# top.net
KiCad netlist of a schematic drawn in EAGLE
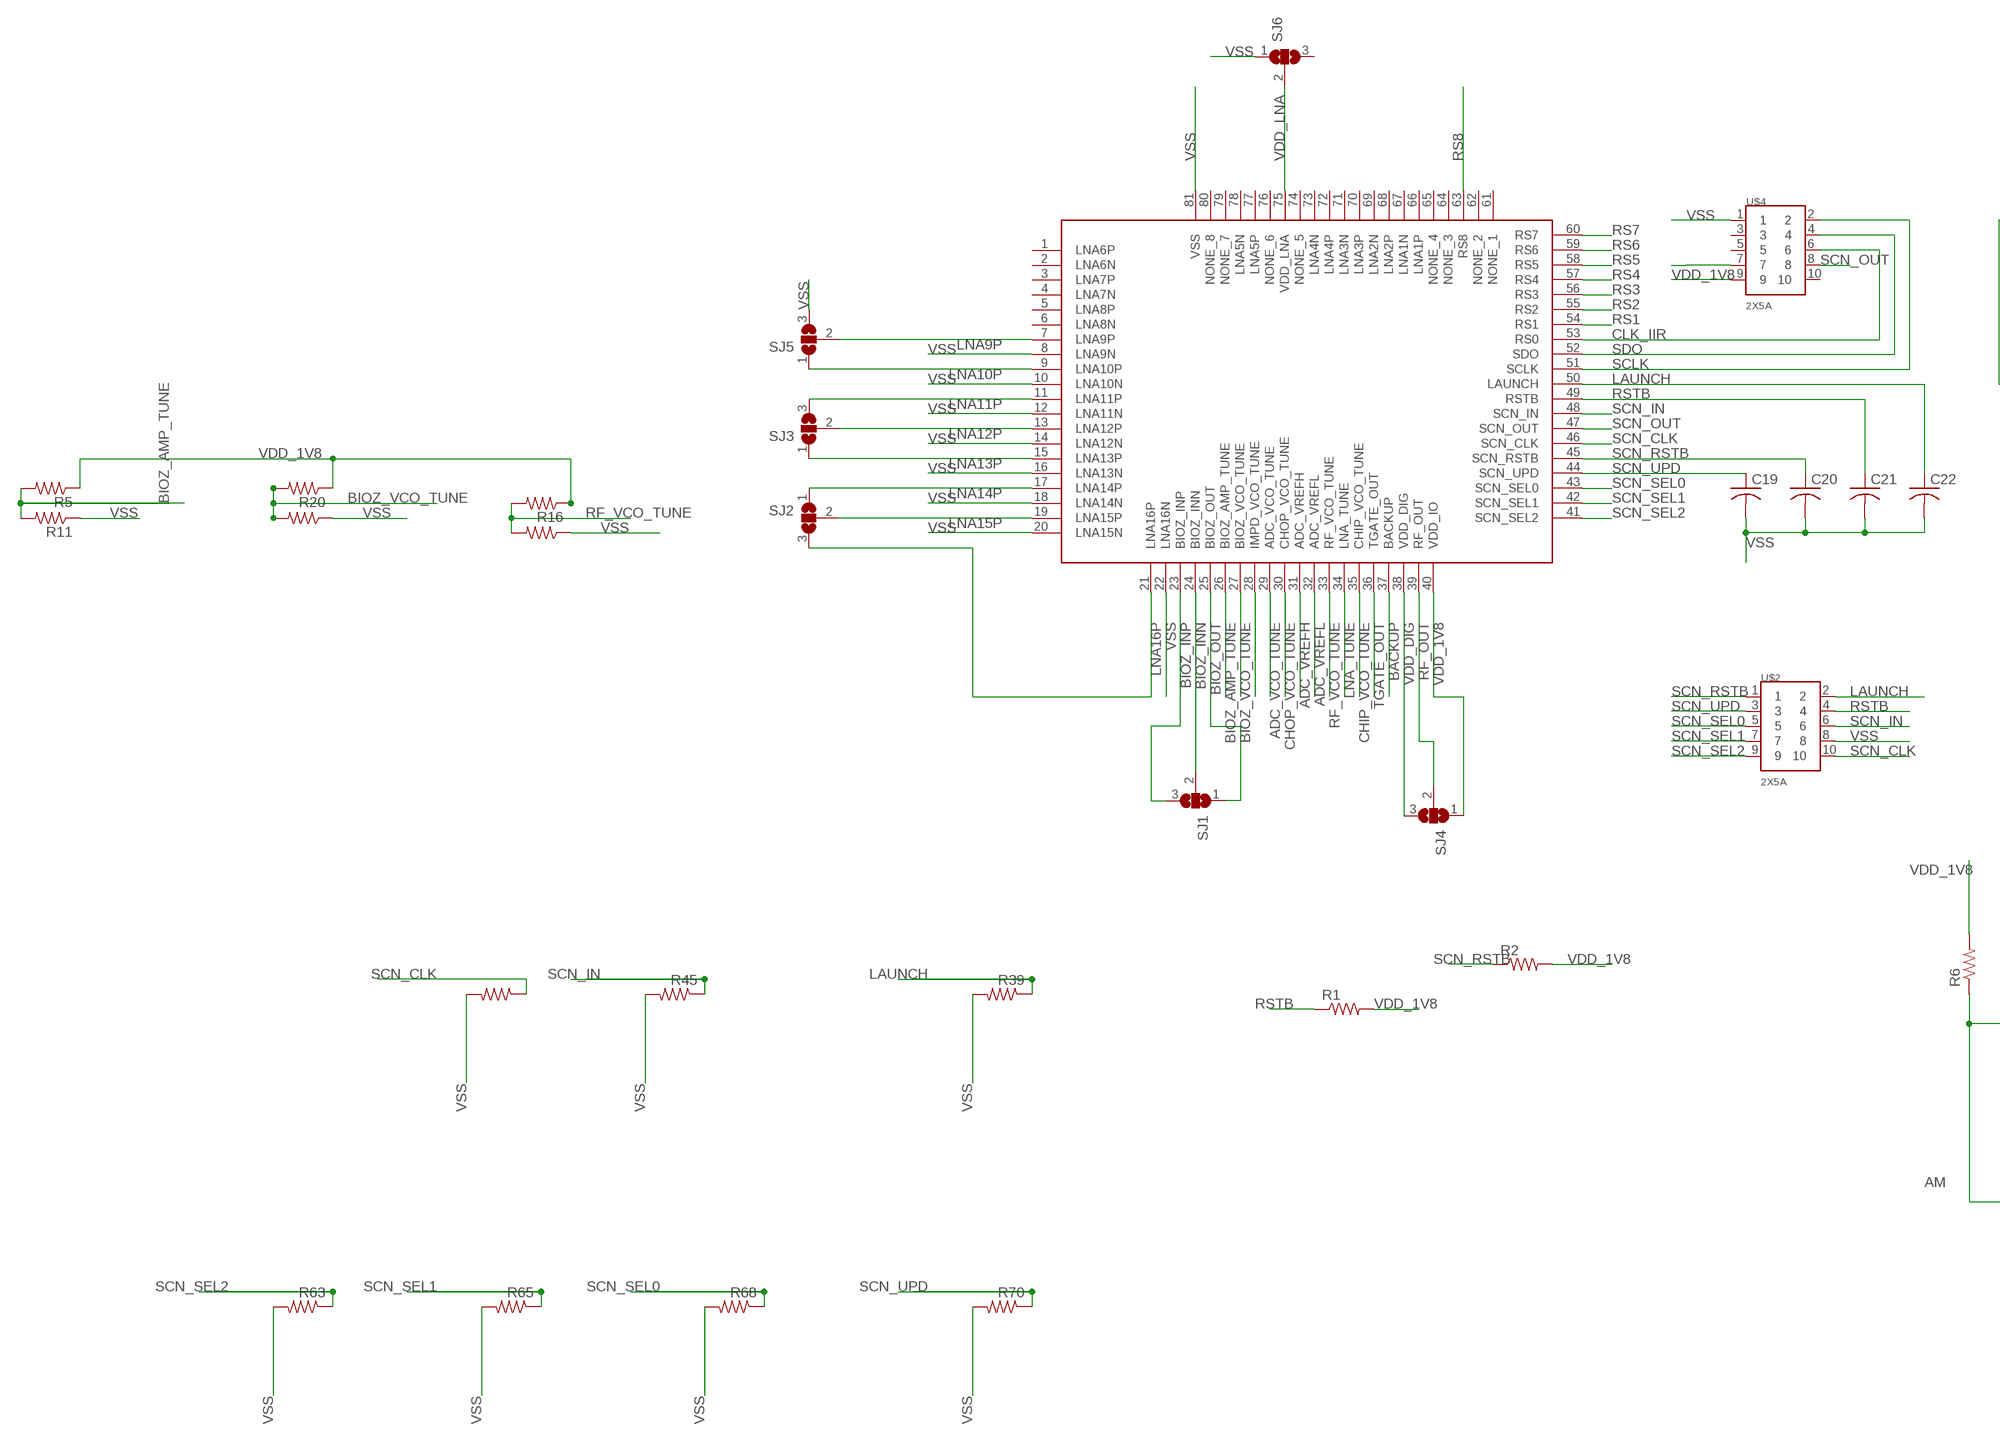
[diagram p0: schematic, sheet 1, part 1 of 2]
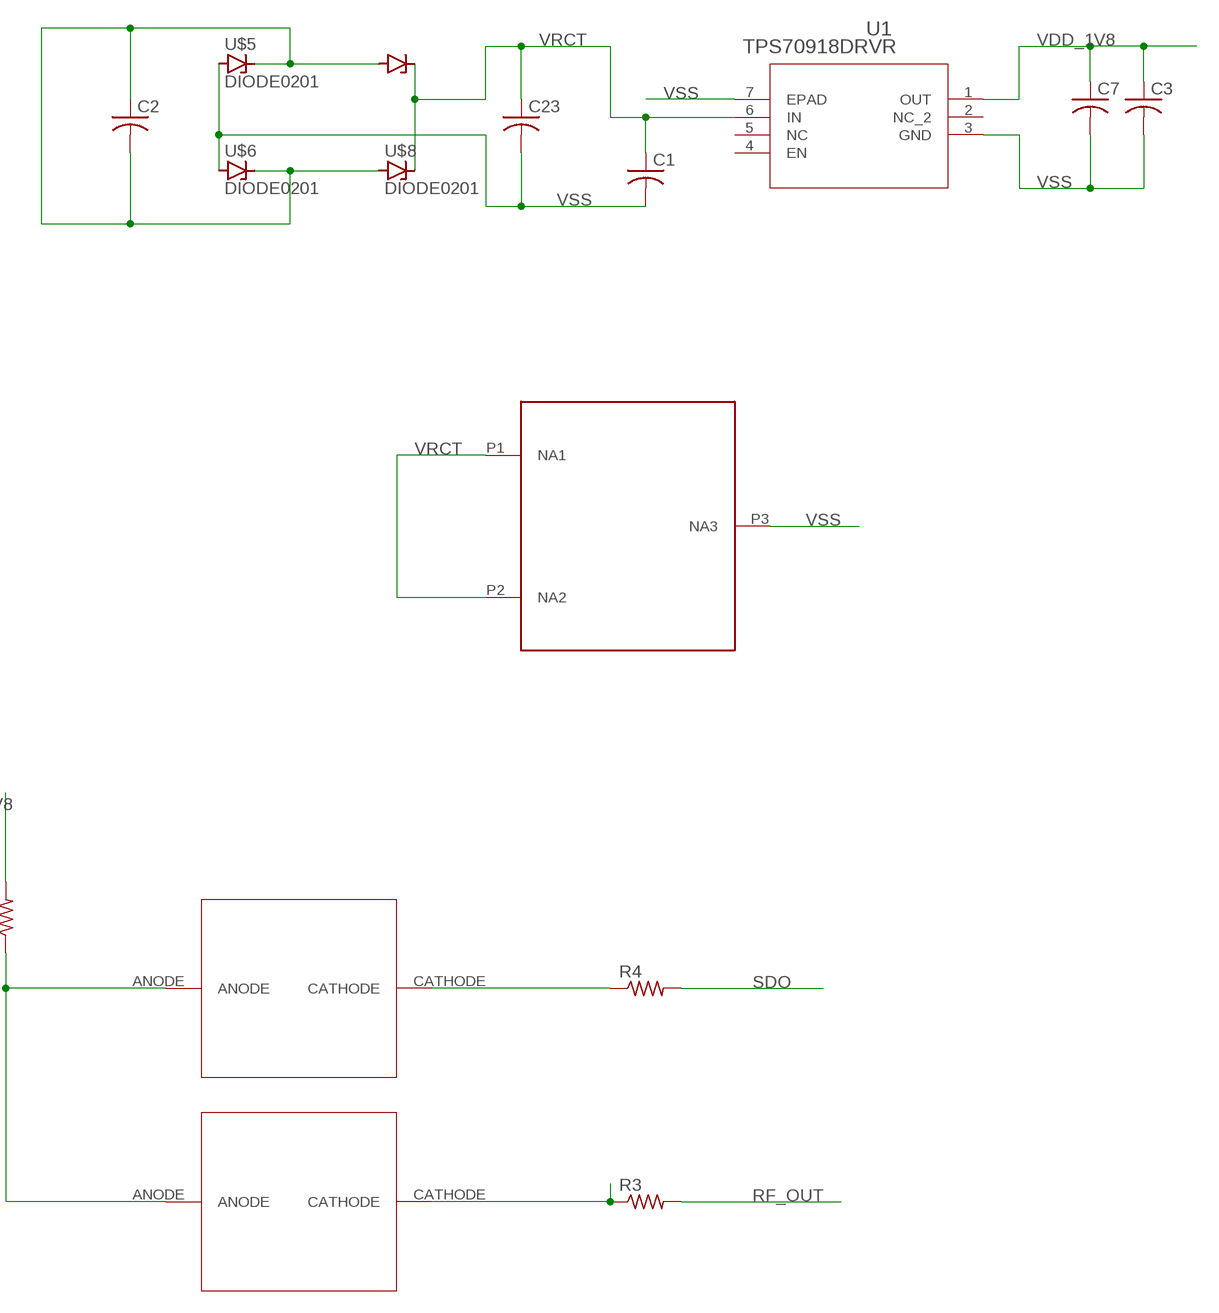
[diagram p1: schematic, sheet 1, part 2 of 2]

(export (version "E")
  (design (tool "Eeschema 10.0.6"))
  (components
    (comp (ref "C1")
      (value "C-USC0402")
      (footprint "eagle-import:C0402")
      (libsource (lib "eagle-import") (part "rcl_334_C-USC0402"))
    )
    (comp (ref "C2")
      (value "C-USC0201")
      (footprint "eagle-import:C0201")
      (libsource (lib "eagle-import") (part "rcl_334_C-USC0201"))
    )
    (comp (ref "C3")
      (value "C-USC0402")
      (footprint "eagle-import:C0402")
      (libsource (lib "eagle-import") (part "rcl_334_C-USC0402"))
    )
    (comp (ref "C7")
      (value "C-USC1210")
      (footprint "eagle-import:C1210")
      (libsource (lib "eagle-import") (part "C-USC1210"))
    )
    (comp (ref "C19")
      (value "C-USC0201")
      (footprint "eagle-import:C0201")
      (libsource (lib "eagle-import") (part "rcl_334_C-USC0201"))
    )
    (comp (ref "C20")
      (value "C-USC0201")
      (footprint "eagle-import:C0201")
      (libsource (lib "eagle-import") (part "rcl_334_C-USC0201"))
    )
    (comp (ref "C21")
      (value "C-USC0201")
      (footprint "eagle-import:C0201")
      (libsource (lib "eagle-import") (part "rcl_334_C-USC0201"))
    )
    (comp (ref "C22")
      (value "C-USC0201")
      (footprint "eagle-import:C0201")
      (libsource (lib "eagle-import") (part "rcl_334_C-USC0201"))
    )
    (comp (ref "C23")
      (value "C-USC1210")
      (footprint "eagle-import:C1210")
      (libsource (lib "eagle-import") (part "C-USC1210"))
    )
    (comp (ref "R1")
      (value "R-US_R0402")
      (footprint "eagle-import:R0402")
      (libsource (lib "eagle-import") (part "R-US_R0402"))
    )
    (comp (ref "R2")
      (value "R-US_R0402")
      (footprint "eagle-import:R0402")
      (libsource (lib "eagle-import") (part "R-US_R0402"))
    )
    (comp (ref "R3")
      (value "R-US_R0402")
      (footprint "eagle-import:R0402")
      (libsource (lib "eagle-import") (part "R-US_R0402"))
    )
    (comp (ref "R4")
      (value "R-US_R0402")
      (footprint "eagle-import:R0402")
      (libsource (lib "eagle-import") (part "R-US_R0402"))
    )
    (comp (ref "R5")
      (value "R-US_R0201")
      (footprint "eagle-import:R0201")
      (libsource (lib "eagle-import") (part "R-US_R0201"))
    )
    (comp (ref "R6")
      (value "R-US_R0402")
      (footprint "eagle-import:R0402")
      (libsource (lib "eagle-import") (part "R-US_R0402"))
    )
    (comp (ref "R11")
      (value "R-US_R0201")
      (footprint "eagle-import:R0201")
      (libsource (lib "eagle-import") (part "R-US_R0201"))
    )
    (comp (ref "R16")
      (value "R-US_R0201")
      (footprint "eagle-import:R0201")
      (libsource (lib "eagle-import") (part "R-US_R0201"))
    )
    (comp (ref "R17")
      (value "R-US_R0201")
      (footprint "eagle-import:R0201")
      (libsource (lib "eagle-import") (part "R-US_R0201"))
    )
    (comp (ref "R20")
      (value "R-US_R0201")
      (footprint "eagle-import:R0201")
      (libsource (lib "eagle-import") (part "R-US_R0201"))
    )
    (comp (ref "R22")
      (value "R-US_R0201")
      (footprint "eagle-import:R0201")
      (libsource (lib "eagle-import") (part "R-US_R0201"))
    )
    (comp (ref "R39")
      (value "R-US_R0402")
      (footprint "eagle-import:R0402")
      (libsource (lib "eagle-import") (part "R-US_R0402"))
    )
    (comp (ref "R45")
      (value "R-US_R0402")
      (footprint "eagle-import:R0402")
      (libsource (lib "eagle-import") (part "R-US_R0402"))
    )
    (comp (ref "R47")
      (value "R-US_R0402")
      (footprint "eagle-import:R0402")
      (libsource (lib "eagle-import") (part "R-US_R0402"))
    )
    (comp (ref "R63")
      (value "R-US_R0402")
      (footprint "eagle-import:R0402")
      (libsource (lib "eagle-import") (part "R-US_R0402"))
    )
    (comp (ref "R65")
      (value "R-US_R0402")
      (footprint "eagle-import:R0402")
      (libsource (lib "eagle-import") (part "R-US_R0402"))
    )
    (comp (ref "R68")
      (value "R-US_R0402")
      (footprint "eagle-import:R0402")
      (libsource (lib "eagle-import") (part "R-US_R0402"))
    )
    (comp (ref "R70")
      (value "R-US_R0402")
      (footprint "eagle-import:R0402")
      (libsource (lib "eagle-import") (part "R-US_R0402"))
    )
    (comp (ref "SJ1")
      (value "SJ2W")
      (footprint "eagle-import:SJ_2")
      (libsource (lib "eagle-import") (part "SJ2W"))
    )
    (comp (ref "SJ2")
      (value "SJ2W")
      (footprint "eagle-import:SJ_2")
      (libsource (lib "eagle-import") (part "SJ2W"))
    )
    (comp (ref "SJ3")
      (value "SJ2W")
      (footprint "eagle-import:SJ_2")
      (libsource (lib "eagle-import") (part "SJ2W"))
    )
    (comp (ref "SJ4")
      (value "SJ2W")
      (footprint "eagle-import:SJ_2")
      (libsource (lib "eagle-import") (part "SJ2W"))
    )
    (comp (ref "SJ5")
      (value "SJ2W")
      (footprint "eagle-import:SJ_2")
      (libsource (lib "eagle-import") (part "SJ2W"))
    )
    (comp (ref "SJ6")
      (value "SJ2W")
      (footprint "eagle-import:SJ_2")
      (libsource (lib "eagle-import") (part "SJ2W"))
    )
    (comp (ref "U$1")
      (value "CHIP_QFN")
      (footprint "eagle-import:QFN50P1200X1200X80-81T900N")
      (libsource (lib "eagle-import") (part "CHIP_QFN"))
    )
    (comp (ref "U$2")
      (value "2X5A")
      (footprint "eagle-import:2X5-FCI_UNSHROUDED")
      (libsource (lib "eagle-import") (part "2X5A"))
    )
    (comp (ref "U$3")
      (value "3030TR")
      (footprint "eagle-import:3030TR")
      (libsource (lib "eagle-import") (part "3030TR"))
    )
    (comp (ref "U$4")
      (value "2X5A")
      (footprint "eagle-import:2X5-FCI_UNSHROUDED")
      (libsource (lib "eagle-import") (part "2X5A"))
    )
    (comp (ref "U$5")
      (value "DIODE0201")
      (footprint "eagle-import:C0201")
      (libsource (lib "eagle-import") (part "DIODE0201"))
    )
    (comp (ref "U$6")
      (value "DIODE0201")
      (footprint "eagle-import:C0201")
      (libsource (lib "eagle-import") (part "DIODE0201"))
    )
    (comp (ref "U$7")
      (value "DIODE0201")
      (footprint "eagle-import:C0201")
      (libsource (lib "eagle-import") (part "DIODE0201"))
    )
    (comp (ref "U$8")
      (value "DIODE0201")
      (footprint "eagle-import:C0201")
      (libsource (lib "eagle-import") (part "DIODE0201"))
    )
    (comp (ref "U$9")
      (value "MSWSE-050-17")
      (footprint "eagle-import:DIODE_MSWSE-050-17")
      (libsource (lib "eagle-import") (part "MSWSE-050-17"))
    )
    (comp (ref "U$10")
      (value "MSWSE-050-17")
      (footprint "eagle-import:DIODE_MSWSE-050-17")
      (libsource (lib "eagle-import") (part "MSWSE-050-17"))
    )
    (comp (ref "U1")
      (value "TPS70918DRVR")
      (footprint "eagle-import:DRV6_1P6X1_TEX")
      (fields (field (name "COPYRIGHT") "Copyright (C) 2023 Ultra Librarian. All rights reserved."))
      (libsource (lib "eagle-import") (part "TPS70918DRVR"))
    )
  )
  (nets
    (net (code "1") (name "/ADC_VCO_TUNE") (class "Default")
      (node (ref "U$1") (pin "29") (pinfunction "ADC_VCO_TUNE_29") (pintype "bidirectional"))
    )
    (net (code "2") (name "/ADC_VREFH") (class "Default")
      (node (ref "U$1") (pin "31") (pinfunction "ADC_VREFH_31") (pintype "bidirectional"))
    )
    (net (code "3") (name "/ADC_VREFL") (class "Default")
      (node (ref "U$1") (pin "32") (pinfunction "ADC_VREFL_32") (pintype "bidirectional"))
    )
    (net (code "4") (name "/AM") (class "Default")
      (node (ref "R6") (pin "1") (pinfunction "1_1") (pintype "passive"))
      (node (ref "U$10") (pin "ANODE") (pinfunction "ANODE_ANODE") (pintype "bidirectional"))
      (node (ref "U$4") (pin "7") (pinfunction "7_7") (pintype "bidirectional"))
      (node (ref "U$9") (pin "ANODE") (pinfunction "ANODE_ANODE") (pintype "bidirectional"))
    )
    (net (code "5") (name "/BACKUP") (class "Default")
      (node (ref "U$1") (pin "37") (pinfunction "BACKUP_37") (pintype "bidirectional"))
    )
    (net (code "6") (name "/BIOZ_AMP_TUNE") (class "Default")
      (node (ref "R11") (pin "2") (pinfunction "2_2") (pintype "passive"))
      (node (ref "R5") (pin "2") (pinfunction "2_2") (pintype "passive"))
      (node (ref "U$1") (pin "26") (pinfunction "BIOZ_AMP_TUNE_26") (pintype "bidirectional"))
    )
    (net (code "7") (name "/BIOZ_INN") (class "Default")
      (node (ref "SJ1") (pin "2") (pinfunction "2_2") (pintype "passive"))
      (node (ref "U$1") (pin "24") (pinfunction "BIOZ_INN_24") (pintype "bidirectional"))
    )
    (net (code "8") (name "/BIOZ_INP") (class "Default")
      (node (ref "SJ1") (pin "3") (pinfunction "3_3") (pintype "passive"))
      (node (ref "U$1") (pin "23") (pinfunction "BIOZ_INP_23") (pintype "bidirectional"))
    )
    (net (code "9") (name "/BIOZ_OUT") (class "Default")
      (node (ref "SJ1") (pin "1") (pinfunction "1_1") (pintype "passive"))
      (node (ref "U$1") (pin "25") (pinfunction "BIOZ_OUT_25") (pintype "bidirectional"))
    )
    (net (code "10") (name "/BIOZ_VCO_TUNE") (class "Default")
      (node (ref "R20") (pin "2") (pinfunction "2_2") (pintype "passive"))
      (node (ref "R22") (pin "2") (pinfunction "2_2") (pintype "passive"))
      (node (ref "U$1") (pin "27") (pinfunction "BIOZ_VCO_TUNE_27") (pintype "bidirectional"))
    )
    (net (code "11") (name "/CHIP_VCO_TUNE") (class "Default")
      (node (ref "U$1") (pin "35") (pinfunction "CHIP_VCO_TUNE_35") (pintype "bidirectional"))
    )
    (net (code "12") (name "/CHOP_VCO_TUNE") (class "Default")
      (node (ref "U$1") (pin "30") (pinfunction "CHOP_VCO_TUNE_30") (pintype "bidirectional"))
    )
    (net (code "13") (name "/CLK_IIR") (class "Default")
      (node (ref "U$1") (pin "53") (pinfunction "RS0_53") (pintype "bidirectional"))
      (node (ref "U$4") (pin "6") (pinfunction "6_6") (pintype "bidirectional"))
    )
    (net (code "14") (name "/LAUNCH") (class "Default")
      (node (ref "C22") (pin "1") (pinfunction "1_1") (pintype "passive"))
      (node (ref "R39") (pin "1") (pinfunction "1_1") (pintype "passive"))
      (node (ref "U$1") (pin "50") (pinfunction "LAUNCH_50") (pintype "bidirectional"))
      (node (ref "U$2") (pin "2") (pinfunction "2_2") (pintype "bidirectional"))
    )
    (net (code "15") (name "/LNA9P") (class "Default")
      (node (ref "SJ5") (pin "2") (pinfunction "2_2") (pintype "passive"))
      (node (ref "U$1") (pin "7") (pinfunction "LNA9P_7") (pintype "bidirectional"))
    )
    (net (code "16") (name "/LNA10P") (class "Default")
      (node (ref "SJ5") (pin "1") (pinfunction "1_1") (pintype "passive"))
      (node (ref "U$1") (pin "9") (pinfunction "LNA10P_9") (pintype "bidirectional"))
    )
    (net (code "17") (name "/LNA11P") (class "Default")
      (node (ref "SJ3") (pin "3") (pinfunction "3_3") (pintype "passive"))
      (node (ref "U$1") (pin "11") (pinfunction "LNA11P_11") (pintype "bidirectional"))
    )
    (net (code "18") (name "/LNA12P") (class "Default")
      (node (ref "SJ3") (pin "2") (pinfunction "2_2") (pintype "passive"))
      (node (ref "U$1") (pin "13") (pinfunction "LNA12P_13") (pintype "bidirectional"))
    )
    (net (code "19") (name "/LNA13P") (class "Default")
      (node (ref "SJ3") (pin "1") (pinfunction "1_1") (pintype "passive"))
      (node (ref "U$1") (pin "15") (pinfunction "LNA13P_15") (pintype "bidirectional"))
    )
    (net (code "20") (name "/LNA14P") (class "Default")
      (node (ref "SJ2") (pin "1") (pinfunction "1_1") (pintype "passive"))
      (node (ref "U$1") (pin "17") (pinfunction "LNA14P_17") (pintype "bidirectional"))
    )
    (net (code "21") (name "/LNA15P") (class "Default")
      (node (ref "SJ2") (pin "2") (pinfunction "2_2") (pintype "passive"))
      (node (ref "U$1") (pin "19") (pinfunction "LNA15P_19") (pintype "bidirectional"))
    )
    (net (code "22") (name "/LNA16P") (class "Default")
      (node (ref "SJ2") (pin "3") (pinfunction "3_3") (pintype "passive"))
      (node (ref "U$1") (pin "21") (pinfunction "LNA16P_21") (pintype "bidirectional"))
    )
    (net (code "23") (name "/LNA_TUNE") (class "Default")
      (node (ref "U$1") (pin "34") (pinfunction "LNA_TUNE_34") (pintype "bidirectional"))
    )
    (net (code "24") (name "/RF_OUT") (class "Default")
      (node (ref "R3") (pin "2") (pinfunction "2_2") (pintype "passive"))
      (node (ref "SJ4") (pin "2") (pinfunction "2_2") (pintype "passive"))
      (node (ref "U$1") (pin "39") (pinfunction "RF_OUT_39") (pintype "bidirectional"))
    )
    (net (code "25") (name "/RF_VCO_TUNE") (class "Default")
      (node (ref "R16") (pin "2") (pinfunction "2_2") (pintype "passive"))
      (node (ref "R17") (pin "2") (pinfunction "2_2") (pintype "passive"))
      (node (ref "U$1") (pin "33") (pinfunction "RF_VCO_TUNE_33") (pintype "bidirectional"))
    )
    (net (code "26") (name "/RS1") (class "Default")
      (node (ref "U$1") (pin "54") (pinfunction "RS1_54") (pintype "bidirectional"))
    )
    (net (code "27") (name "/RS2") (class "Default")
      (node (ref "U$1") (pin "55") (pinfunction "RS2_55") (pintype "bidirectional"))
    )
    (net (code "28") (name "/RS3") (class "Default")
      (node (ref "U$1") (pin "56") (pinfunction "RS3_56") (pintype "bidirectional"))
    )
    (net (code "29") (name "/RS4") (class "Default")
      (node (ref "U$1") (pin "57") (pinfunction "RS4_57") (pintype "bidirectional"))
    )
    (net (code "30") (name "/RS5") (class "Default")
      (node (ref "U$1") (pin "58") (pinfunction "RS5_58") (pintype "bidirectional"))
    )
    (net (code "31") (name "/RS6") (class "Default")
      (node (ref "U$1") (pin "59") (pinfunction "RS6_59") (pintype "bidirectional"))
    )
    (net (code "32") (name "/RS7") (class "Default")
      (node (ref "U$1") (pin "60") (pinfunction "RS7_60") (pintype "bidirectional"))
    )
    (net (code "33") (name "/RS8") (class "Default")
      (node (ref "U$1") (pin "63") (pinfunction "RS8_63") (pintype "bidirectional"))
    )
    (net (code "34") (name "/RSTB") (class "Default")
      (node (ref "C21") (pin "1") (pinfunction "1_1") (pintype "passive"))
      (node (ref "R1") (pin "1") (pinfunction "1_1") (pintype "passive"))
      (node (ref "U$1") (pin "49") (pinfunction "RSTB_49") (pintype "bidirectional"))
      (node (ref "U$2") (pin "4") (pinfunction "4_4") (pintype "bidirectional"))
    )
    (net (code "35") (name "/SCLK") (class "Default")
      (node (ref "U$1") (pin "51") (pinfunction "SCLK_51") (pintype "bidirectional"))
      (node (ref "U$4") (pin "2") (pinfunction "2_2") (pintype "bidirectional"))
    )
    (net (code "36") (name "/SCN_CLK") (class "Default")
      (node (ref "R47") (pin "1") (pinfunction "1_1") (pintype "passive"))
      (node (ref "U$1") (pin "46") (pinfunction "SCN_CLK_46") (pintype "bidirectional"))
      (node (ref "U$2") (pin "10") (pinfunction "10_10") (pintype "bidirectional"))
    )
    (net (code "37") (name "/SCN_IN") (class "Default")
      (node (ref "R45") (pin "1") (pinfunction "1_1") (pintype "passive"))
      (node (ref "U$1") (pin "48") (pinfunction "SCN_IN_48") (pintype "bidirectional"))
      (node (ref "U$2") (pin "6") (pinfunction "6_6") (pintype "bidirectional"))
    )
    (net (code "38") (name "/SCN_OUT") (class "Default")
      (node (ref "U$1") (pin "47") (pinfunction "SCN_OUT_47") (pintype "bidirectional"))
      (node (ref "U$4") (pin "8") (pinfunction "8_8") (pintype "bidirectional"))
    )
    (net (code "39") (name "/SCN_RSTB") (class "Default")
      (node (ref "C20") (pin "1") (pinfunction "1_1") (pintype "passive"))
      (node (ref "R2") (pin "1") (pinfunction "1_1") (pintype "passive"))
      (node (ref "U$1") (pin "45") (pinfunction "SCN_RSTB_45") (pintype "bidirectional"))
      (node (ref "U$2") (pin "1") (pinfunction "1_1") (pintype "bidirectional"))
    )
    (net (code "40") (name "/SCN_SEL0") (class "Default")
      (node (ref "R68") (pin "1") (pinfunction "1_1") (pintype "passive"))
      (node (ref "U$1") (pin "43") (pinfunction "SCN_SEL0_43") (pintype "bidirectional"))
      (node (ref "U$2") (pin "5") (pinfunction "5_5") (pintype "bidirectional"))
    )
    (net (code "41") (name "/SCN_SEL1") (class "Default")
      (node (ref "R65") (pin "1") (pinfunction "1_1") (pintype "passive"))
      (node (ref "U$1") (pin "42") (pinfunction "SCN_SEL1_42") (pintype "bidirectional"))
      (node (ref "U$2") (pin "7") (pinfunction "7_7") (pintype "bidirectional"))
    )
    (net (code "42") (name "/SCN_SEL2") (class "Default")
      (node (ref "R63") (pin "1") (pinfunction "1_1") (pintype "passive"))
      (node (ref "U$1") (pin "41") (pinfunction "SCN_SEL2_41") (pintype "bidirectional"))
      (node (ref "U$2") (pin "9") (pinfunction "9_9") (pintype "bidirectional"))
    )
    (net (code "43") (name "/SCN_UPD") (class "Default")
      (node (ref "C19") (pin "1") (pinfunction "1_1") (pintype "passive"))
      (node (ref "R70") (pin "1") (pinfunction "1_1") (pintype "passive"))
      (node (ref "U$1") (pin "44") (pinfunction "SCN_UPD_44") (pintype "bidirectional"))
      (node (ref "U$2") (pin "3") (pinfunction "3_3") (pintype "bidirectional"))
    )
    (net (code "44") (name "/SDO") (class "Default")
      (node (ref "R4") (pin "2") (pinfunction "2_2") (pintype "passive"))
      (node (ref "U$1") (pin "52") (pinfunction "SDO_52") (pintype "bidirectional"))
      (node (ref "U$4") (pin "4") (pinfunction "4_4") (pintype "bidirectional"))
    )
    (net (code "45") (name "/TGATE_OUT") (class "Default")
      (node (ref "U$1") (pin "36") (pinfunction "TGATE_OUT_36") (pintype "bidirectional"))
    )
    (net (code "46") (name "/VDD_1V8") (class "Default")
      (node (ref "C3") (pin "1") (pinfunction "1_1") (pintype "passive"))
      (node (ref "C7") (pin "1") (pinfunction "1_1") (pintype "passive"))
      (node (ref "R1") (pin "2") (pinfunction "2_2") (pintype "passive"))
      (node (ref "R16") (pin "1") (pinfunction "1_1") (pintype "passive"))
      (node (ref "R2") (pin "2") (pinfunction "2_2") (pintype "passive"))
      (node (ref "R20") (pin "1") (pinfunction "1_1") (pintype "passive"))
      (node (ref "R5") (pin "1") (pinfunction "1_1") (pintype "passive"))
      (node (ref "R6") (pin "2") (pinfunction "2_2") (pintype "passive"))
      (node (ref "SJ4") (pin "1") (pinfunction "1_1") (pintype "passive"))
      (node (ref "U$1") (pin "40") (pinfunction "VDD_IO_40") (pintype "bidirectional"))
      (node (ref "U$4") (pin "9") (pinfunction "9_9") (pintype "bidirectional"))
      (node (ref "U1") (pin "1") (pinfunction "OUT_1") (pintype "output"))
    )
    (net (code "47") (name "/VDD_DIG") (class "Default")
      (node (ref "SJ4") (pin "3") (pinfunction "3_3") (pintype "passive"))
      (node (ref "U$1") (pin "38") (pinfunction "VDD_DIG_38") (pintype "bidirectional"))
    )
    (net (code "48") (name "/VDD_LNA") (class "Default")
      (node (ref "SJ6") (pin "2") (pinfunction "2_2") (pintype "passive"))
      (node (ref "U$1") (pin "75") (pinfunction "VDD_LNA_75") (pintype "bidirectional"))
    )
    (net (code "49") (name "/VRCT") (class "Default")
      (node (ref "C1") (pin "1") (pinfunction "1_1") (pintype "passive"))
      (node (ref "C23") (pin "1") (pinfunction "1_1") (pintype "passive"))
      (node (ref "U$3") (pin "P1") (pinfunction "NA1_P1") (pintype "bidirectional"))
      (node (ref "U$3") (pin "P2") (pinfunction "NA2_P2") (pintype "bidirectional"))
      (node (ref "U$7") (pin "2") (pinfunction "C_2") (pintype "passive"))
      (node (ref "U$8") (pin "2") (pinfunction "C_2") (pintype "passive"))
      (node (ref "U1") (pin "6") (pinfunction "IN_6") (pintype "input"))
    )
    (net (code "50") (name "/VSS") (class "Default")
      (node (ref "C1") (pin "2") (pinfunction "2_2") (pintype "passive"))
      (node (ref "C19") (pin "2") (pinfunction "2_2") (pintype "passive"))
      (node (ref "C20") (pin "2") (pinfunction "2_2") (pintype "passive"))
      (node (ref "C21") (pin "2") (pinfunction "2_2") (pintype "passive"))
      (node (ref "C22") (pin "2") (pinfunction "2_2") (pintype "passive"))
      (node (ref "C23") (pin "2") (pinfunction "2_2") (pintype "passive"))
      (node (ref "C3") (pin "2") (pinfunction "2_2") (pintype "passive"))
      (node (ref "C7") (pin "2") (pinfunction "2_2") (pintype "passive"))
      (node (ref "R11") (pin "1") (pinfunction "1_1") (pintype "passive"))
      (node (ref "R17") (pin "1") (pinfunction "1_1") (pintype "passive"))
      (node (ref "R22") (pin "1") (pinfunction "1_1") (pintype "passive"))
      (node (ref "R39") (pin "2") (pinfunction "2_2") (pintype "passive"))
      (node (ref "R45") (pin "2") (pinfunction "2_2") (pintype "passive"))
      (node (ref "R47") (pin "2") (pinfunction "2_2") (pintype "passive"))
      (node (ref "R63") (pin "2") (pinfunction "2_2") (pintype "passive"))
      (node (ref "R65") (pin "2") (pinfunction "2_2") (pintype "passive"))
      (node (ref "R68") (pin "2") (pinfunction "2_2") (pintype "passive"))
      (node (ref "R70") (pin "2") (pinfunction "2_2") (pintype "passive"))
      (node (ref "SJ5") (pin "3") (pinfunction "3_3") (pintype "passive"))
      (node (ref "SJ6") (pin "1") (pinfunction "1_1") (pintype "passive"))
      (node (ref "U$1") (pin "10") (pinfunction "LNA10N_10") (pintype "bidirectional"))
      (node (ref "U$1") (pin "12") (pinfunction "LNA11N_12") (pintype "bidirectional"))
      (node (ref "U$1") (pin "14") (pinfunction "LNA12N_14") (pintype "bidirectional"))
      (node (ref "U$1") (pin "16") (pinfunction "LNA13N_16") (pintype "bidirectional"))
      (node (ref "U$1") (pin "18") (pinfunction "LNA14N_18") (pintype "bidirectional"))
      (node (ref "U$1") (pin "20") (pinfunction "LNA15N_20") (pintype "bidirectional"))
      (node (ref "U$1") (pin "22") (pinfunction "LNA16N_22") (pintype "bidirectional"))
      (node (ref "U$1") (pin "8") (pinfunction "LNA9N_8") (pintype "bidirectional"))
      (node (ref "U$1") (pin "81") (pinfunction "VSS_81") (pintype "bidirectional"))
      (node (ref "U$2") (pin "8") (pinfunction "8_8") (pintype "bidirectional"))
      (node (ref "U$3") (pin "P3") (pinfunction "NA3_P3") (pintype "bidirectional"))
      (node (ref "U$4") (pin "1") (pinfunction "1_1") (pintype "bidirectional"))
      (node (ref "U$5") (pin "1") (pinfunction "A_1") (pintype "passive"))
      (node (ref "U$6") (pin "1") (pinfunction "A_1") (pintype "passive"))
      (node (ref "U1") (pin "3") (pinfunction "GND_3") (pintype "power_in"))
      (node (ref "U1") (pin "7") (pinfunction "EPAD_7") (pintype "passive"))
    )
    (net (code "51") (name "Net-(R3-Pad1)") (class "Default")
      (node (ref "R3") (pin "1") (pinfunction "1_1") (pintype "passive"))
      (node (ref "U$10") (pin "CATHODE") (pinfunction "CATHODE_CATHODE") (pintype "bidirectional"))
    )
    (net (code "52") (name "Net-(R4-Pad1)") (class "Default")
      (node (ref "R4") (pin "1") (pinfunction "1_1") (pintype "passive"))
      (node (ref "U$9") (pin "CATHODE") (pinfunction "CATHODE_CATHODE") (pintype "bidirectional"))
    )
    (net (code "53") (name "Net-(U$5-C)") (class "Default")
      (node (ref "C2") (pin "1") (pinfunction "1_1") (pintype "passive"))
      (node (ref "C2") (pin "2") (pinfunction "2_2") (pintype "passive"))
      (node (ref "U$5") (pin "2") (pinfunction "C_2") (pintype "passive"))
      (node (ref "U$6") (pin "2") (pinfunction "C_2") (pintype "passive"))
      (node (ref "U$7") (pin "1") (pinfunction "A_1") (pintype "passive"))
      (node (ref "U$8") (pin "1") (pinfunction "A_1") (pintype "passive"))
    )
    (net (code "54") (name "unconnected-(SJ6-Pad3)") (class "Default")
      (node (ref "SJ6") (pin "3") (pinfunction "3_3") (pintype "passive"))
    )
    (net (code "55") (name "unconnected-(U$1-IMPD_VCO_TUNE-Pad28)") (class "Default")
      (node (ref "U$1") (pin "28") (pinfunction "IMPD_VCO_TUNE_28") (pintype "bidirectional"))
    )
    (net (code "56") (name "unconnected-(U$1-LNA1N-Pad67)") (class "Default")
      (node (ref "U$1") (pin "67") (pinfunction "LNA1N_67") (pintype "bidirectional"))
    )
    (net (code "57") (name "unconnected-(U$1-LNA1P-Pad66)") (class "Default")
      (node (ref "U$1") (pin "66") (pinfunction "LNA1P_66") (pintype "bidirectional"))
    )
    (net (code "58") (name "unconnected-(U$1-LNA2N-Pad69)") (class "Default")
      (node (ref "U$1") (pin "69") (pinfunction "LNA2N_69") (pintype "bidirectional"))
    )
    (net (code "59") (name "unconnected-(U$1-LNA2P-Pad68)") (class "Default")
      (node (ref "U$1") (pin "68") (pinfunction "LNA2P_68") (pintype "bidirectional"))
    )
    (net (code "60") (name "unconnected-(U$1-LNA3N-Pad71)") (class "Default")
      (node (ref "U$1") (pin "71") (pinfunction "LNA3N_71") (pintype "bidirectional"))
    )
    (net (code "61") (name "unconnected-(U$1-LNA3P-Pad70)") (class "Default")
      (node (ref "U$1") (pin "70") (pinfunction "LNA3P_70") (pintype "bidirectional"))
    )
    (net (code "62") (name "unconnected-(U$1-LNA4N-Pad73)") (class "Default")
      (node (ref "U$1") (pin "73") (pinfunction "LNA4N_73") (pintype "bidirectional"))
    )
    (net (code "63") (name "unconnected-(U$1-LNA4P-Pad72)") (class "Default")
      (node (ref "U$1") (pin "72") (pinfunction "LNA4P_72") (pintype "bidirectional"))
    )
    (net (code "64") (name "unconnected-(U$1-LNA5N-Pad78)") (class "Default")
      (node (ref "U$1") (pin "78") (pinfunction "LNA5N_78") (pintype "bidirectional"))
    )
    (net (code "65") (name "unconnected-(U$1-LNA5P-Pad77)") (class "Default")
      (node (ref "U$1") (pin "77") (pinfunction "LNA5P_77") (pintype "bidirectional"))
    )
    (net (code "66") (name "unconnected-(U$1-LNA6N-Pad2)") (class "Default")
      (node (ref "U$1") (pin "2") (pinfunction "LNA6N_2") (pintype "bidirectional"))
    )
    (net (code "67") (name "unconnected-(U$1-LNA6P-Pad1)") (class "Default")
      (node (ref "U$1") (pin "1") (pinfunction "LNA6P_1") (pintype "bidirectional"))
    )
    (net (code "68") (name "unconnected-(U$1-LNA7N-Pad4)") (class "Default")
      (node (ref "U$1") (pin "4") (pinfunction "LNA7N_4") (pintype "bidirectional"))
    )
    (net (code "69") (name "unconnected-(U$1-LNA7P-Pad3)") (class "Default")
      (node (ref "U$1") (pin "3") (pinfunction "LNA7P_3") (pintype "bidirectional"))
    )
    (net (code "70") (name "unconnected-(U$1-LNA8N-Pad6)") (class "Default")
      (node (ref "U$1") (pin "6") (pinfunction "LNA8N_6") (pintype "bidirectional"))
    )
    (net (code "71") (name "unconnected-(U$1-LNA8P-Pad5)") (class "Default")
      (node (ref "U$1") (pin "5") (pinfunction "LNA8P_5") (pintype "bidirectional"))
    )
    (net (code "72") (name "unconnected-(U$1-NONE_1-Pad61)") (class "Default")
      (node (ref "U$1") (pin "61") (pinfunction "NONE_1_61") (pintype "bidirectional"))
    )
    (net (code "73") (name "unconnected-(U$1-NONE_2-Pad62)") (class "Default")
      (node (ref "U$1") (pin "62") (pinfunction "NONE_2_62") (pintype "bidirectional"))
    )
    (net (code "74") (name "unconnected-(U$1-NONE_3-Pad64)") (class "Default")
      (node (ref "U$1") (pin "64") (pinfunction "NONE_3_64") (pintype "bidirectional"))
    )
    (net (code "75") (name "unconnected-(U$1-NONE_4-Pad65)") (class "Default")
      (node (ref "U$1") (pin "65") (pinfunction "NONE_4_65") (pintype "bidirectional"))
    )
    (net (code "76") (name "unconnected-(U$1-NONE_5-Pad74)") (class "Default")
      (node (ref "U$1") (pin "74") (pinfunction "NONE_5_74") (pintype "bidirectional"))
    )
    (net (code "77") (name "unconnected-(U$1-NONE_6-Pad76)") (class "Default")
      (node (ref "U$1") (pin "76") (pinfunction "NONE_6_76") (pintype "bidirectional"))
    )
    (net (code "78") (name "unconnected-(U$1-NONE_7-Pad79)") (class "Default")
      (node (ref "U$1") (pin "79") (pinfunction "NONE_7_79") (pintype "bidirectional"))
    )
    (net (code "79") (name "unconnected-(U$1-NONE_8-Pad80)") (class "Default")
      (node (ref "U$1") (pin "80") (pinfunction "NONE_8_80") (pintype "bidirectional"))
    )
    (net (code "80") (name "unconnected-(U$4-Pad3)") (class "Default")
      (node (ref "U$4") (pin "3") (pinfunction "3_3") (pintype "bidirectional"))
    )
    (net (code "81") (name "unconnected-(U$4-Pad5)") (class "Default")
      (node (ref "U$4") (pin "5") (pinfunction "5_5") (pintype "bidirectional"))
    )
    (net (code "82") (name "unconnected-(U$4-Pad10)") (class "Default")
      (node (ref "U$4") (pin "10") (pinfunction "10_10") (pintype "bidirectional"))
    )
    (net (code "83") (name "unconnected-(U1-EN-Pad4)") (class "Default")
      (node (ref "U1") (pin "4") (pinfunction "EN_4") (pintype "input"))
    )
    (net (code "84") (name "unconnected-(U1-NC-Pad5)") (class "Default")
      (node (ref "U1") (pin "5") (pinfunction "NC_5") (pintype "no_connect"))
    )
    (net (code "85") (name "unconnected-(U1-NC_2-Pad2)") (class "Default")
      (node (ref "U1") (pin "2") (pinfunction "NC_2_2") (pintype "no_connect"))
    )
  )
)
